# THS4302.net
KiCad netlist of a schematic drawn in Altium Designer
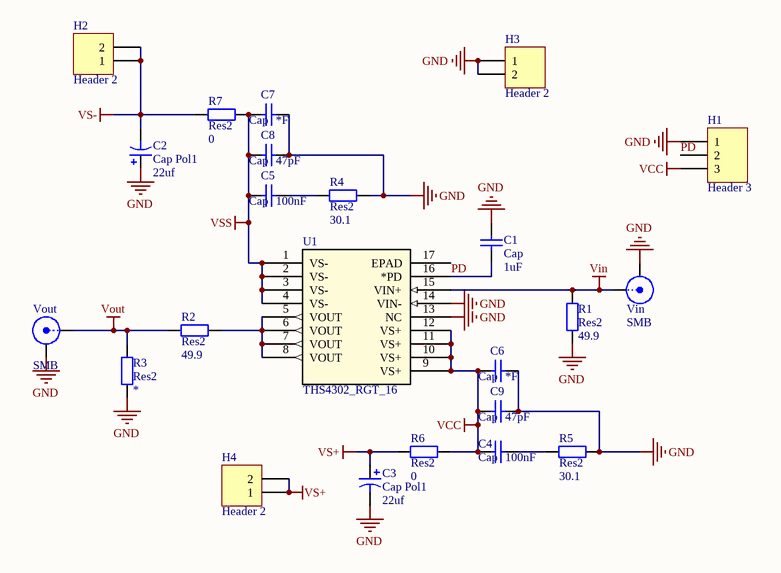
[diagram p0: THS4302.SchDoc]

(export (version "E")
  (design (tool "Eeschema 10.0.6"))
  (components
    (comp (ref "C1")
      (value "Cap")
      (footprint "0805C")
      (description "Capacitor")
      (fields (field (name "ALTIUM_VALUE") "1uF") (field (name "PUBLISHER") "Altium Limited"))
      (libsource (lib "Miscellaneous Devices") (part "Cap"))
    )
    (comp (ref "C2")
      (value "Cap Pol1")
      (footprint "CAP_SMD_3216")
      (description "Polarized Capacitor (Radial)")
      (fields (field (name "ALTIUM_VALUE") "22uf") (field (name "PUBLISHER") "Altium Limited"))
      (libsource (lib "Miscellaneous Devices") (part "Cap Pol1"))
    )
    (comp (ref "C3")
      (value "Cap Pol1")
      (footprint "CAP_SMD_3216")
      (description "Polarized Capacitor (Radial)")
      (fields (field (name "ALTIUM_VALUE") "22uf") (field (name "PUBLISHER") "Altium Limited"))
      (libsource (lib "Miscellaneous Devices") (part "Cap Pol1"))
    )
    (comp (ref "C4")
      (value "Cap")
      (footprint "0805C")
      (description "Capacitor")
      (fields (field (name "ALTIUM_VALUE") "100nF") (field (name "PUBLISHER") "Altium Limited"))
      (libsource (lib "Miscellaneous Devices") (part "Cap"))
    )
    (comp (ref "C5")
      (value "Cap")
      (footprint "0805C")
      (description "Capacitor")
      (fields (field (name "ALTIUM_VALUE") "100nF") (field (name "PUBLISHER") "Altium Limited"))
      (libsource (lib "Miscellaneous Devices") (part "Cap"))
    )
    (comp (ref "C6")
      (value "Cap")
      (footprint "CAP_SMD_3216")
      (description "Capacitor")
      (fields (field (name "ALTIUM_VALUE") "*F") (field (name "PUBLISHER") "Altium Limited"))
      (libsource (lib "Miscellaneous Devices") (part "Cap"))
    )
    (comp (ref "C7")
      (value "Cap")
      (footprint "CAP_SMD_3216")
      (description "Capacitor")
      (fields (field (name "ALTIUM_VALUE") "*F") (field (name "PUBLISHER") "Altium Limited"))
      (libsource (lib "Miscellaneous Devices") (part "Cap"))
    )
    (comp (ref "C8")
      (value "Cap")
      (footprint "0805C")
      (description "Capacitor")
      (fields (field (name "ALTIUM_VALUE") "47pF") (field (name "PUBLISHER") "Altium Limited"))
      (libsource (lib "Miscellaneous Devices") (part "Cap"))
    )
    (comp (ref "C9")
      (value "Cap")
      (footprint "0805C")
      (description "Capacitor")
      (fields (field (name "ALTIUM_VALUE") "47pF") (field (name "PUBLISHER") "Altium Limited"))
      (libsource (lib "Miscellaneous Devices") (part "Cap"))
    )
    (comp (ref "H1")
      (value "Header 3")
      (footprint "HDR1X3")
      (description "Header, 3-Pin")
      (fields (field (name "PUBLISHER") "Altium Limited"))
      (libsource (lib "Miscellaneous Connectors") (part "Header 3"))
    )
    (comp (ref "H2")
      (value "Header 2")
      (footprint "HDR1X2")
      (description "Header, 2-Pin")
      (fields (field (name "PUBLISHER") "Altium Limited"))
      (libsource (lib "Miscellaneous Connectors") (part "Header 2"))
    )
    (comp (ref "H3")
      (value "Header 2")
      (footprint "HDR1X2")
      (description "Header, 2-Pin")
      (fields (field (name "PUBLISHER") "Altium Limited"))
      (libsource (lib "") (part "Header 2_1"))
    )
    (comp (ref "H4")
      (value "Header 2")
      (footprint "HDR1X2")
      (description "Header, 2-Pin")
      (fields (field (name "PUBLISHER") "Altium Limited"))
      (libsource (lib "Miscellaneous Connectors") (part "Header 2"))
    )
    (comp (ref "R1")
      (value "Res2")
      (footprint "0805R")
      (description "Resistor")
      (fields (field (name "ALTIUM_VALUE") "49.9") (field (name "PUBLISHER") "Altium Limited"))
      (libsource (lib "") (part "Res2_1"))
    )
    (comp (ref "R2")
      (value "Res2")
      (footprint "0805R")
      (description "Resistor")
      (fields (field (name "ALTIUM_VALUE") "49.9") (field (name "PUBLISHER") "Altium Limited"))
      (libsource (lib "Miscellaneous Devices") (part "Res2"))
    )
    (comp (ref "R3")
      (value "Res2")
      (footprint "0805R")
      (description "Resistor")
      (fields (field (name "ALTIUM_VALUE") "*") (field (name "PUBLISHER") "Altium Limited"))
      (libsource (lib "") (part "Res2_2"))
    )
    (comp (ref "R4")
      (value "Res2")
      (footprint "0805R")
      (description "Resistor")
      (fields (field (name "ALTIUM_VALUE") "30.1") (field (name "PUBLISHER") "Altium Limited"))
      (libsource (lib "Miscellaneous Devices") (part "Res2"))
    )
    (comp (ref "R5")
      (value "Res2")
      (footprint "0805R")
      (description "Resistor")
      (fields (field (name "ALTIUM_VALUE") "30.1") (field (name "PUBLISHER") "Altium Limited"))
      (libsource (lib "Miscellaneous Devices") (part "Res2"))
    )
    (comp (ref "R6")
      (value "Res2")
      (footprint "0805R")
      (description "Resistor")
      (fields (field (name "ALTIUM_VALUE") "0") (field (name "PUBLISHER") "Altium Limited"))
      (libsource (lib "Miscellaneous Devices") (part "Res2"))
    )
    (comp (ref "R7")
      (value "Res2")
      (footprint "0805R")
      (description "Resistor")
      (fields (field (name "ALTIUM_VALUE") "0") (field (name "PUBLISHER") "Altium Limited"))
      (libsource (lib "Miscellaneous Devices") (part "Res2"))
    )
    (comp (ref "U1")
      (value "THS4302_RGT_16")
      (footprint "RGT16_1P45X1P45")
      (description "Imported")
      (fields
        (field (name "MANUFACTURER_PART_NUMBER") "ths4302_rgt_16")
        (field (name "GENERIC_PART_NUMBER") "THS4302")
      )
      (libsource (lib "THS4302") (part "THS4302_RGT_16"))
    )
    (comp (ref "Vin")
      (value "SMB")
      (footprint "SMB_V-RJ45")
      (description "SMB Straight Connector")
      (fields (field (name "PUBLISHER") "Altium Limited"))
      (libsource (lib "Miscellaneous Connectors") (part "SMB"))
    )
    (comp (ref "Vout")
      (value "SMB")
      (footprint "SMB_V-RJ45")
      (description "SMB Straight Connector")
      (fields (field (name "PUBLISHER") "Altium Limited"))
      (libsource (lib "Miscellaneous Connectors") (part "SMB"))
    )
  )
  (nets
    (net (code "1") (name "/PD") (class "Default")
      (node (ref "C1") (pin "1") (pinfunction "1_1") (pintype "passive"))
      (node (ref "H1") (pin "2") (pinfunction "2_2") (pintype "passive"))
      (node (ref "U1") (pin "16") (pinfunction "*PD_16") (pintype "passive"))
    )
    (net (code "2") (name "GND") (class "Default")
      (node (ref "C1") (pin "2") (pinfunction "2_2") (pintype "passive"))
      (node (ref "C2") (pin "1") (pinfunction "1_1") (pintype "passive"))
      (node (ref "C3") (pin "2") (pinfunction "2_2") (pintype "passive"))
      (node (ref "C6") (pin "2") (pinfunction "2_2") (pintype "passive"))
      (node (ref "C7") (pin "2") (pinfunction "2_2") (pintype "passive"))
      (node (ref "C8") (pin "2") (pinfunction "2_2") (pintype "passive"))
      (node (ref "C9") (pin "2") (pinfunction "2_2") (pintype "passive"))
      (node (ref "H1") (pin "1") (pinfunction "1_1") (pintype "passive"))
      (node (ref "H3") (pin "1") (pinfunction "1_1") (pintype "passive"))
      (node (ref "H3") (pin "2") (pinfunction "2_2") (pintype "passive"))
      (node (ref "R1") (pin "2") (pinfunction "2_2") (pintype "passive"))
      (node (ref "R3") (pin "1") (pinfunction "1_1") (pintype "passive"))
      (node (ref "R4") (pin "2") (pinfunction "2_2") (pintype "passive"))
      (node (ref "R5") (pin "2") (pinfunction "2_2") (pintype "passive"))
      (node (ref "U1") (pin "13") (pinfunction "NC_13") (pintype "passive"))
      (node (ref "U1") (pin "14") (pinfunction "VIN-_14") (pintype "input"))
      (node (ref "Vin") (pin "2") (pinfunction "Y_2") (pintype "passive"))
      (node (ref "Vout") (pin "2") (pinfunction "Y_2") (pintype "passive"))
    )
    (net (code "3") (name "Net-(C4-Pad2)") (class "Default")
      (node (ref "C4") (pin "2") (pinfunction "2_2") (pintype "passive"))
      (node (ref "R5") (pin "1") (pinfunction "1_1") (pintype "passive"))
    )
    (net (code "4") (name "Net-(C5-Pad2)") (class "Default")
      (node (ref "C5") (pin "2") (pinfunction "2_2") (pintype "passive"))
      (node (ref "R4") (pin "1") (pinfunction "1_1") (pintype "passive"))
    )
    (net (code "5") (name "Net-(R2-Pad2)") (class "Default")
      (node (ref "R2") (pin "2") (pinfunction "2_2") (pintype "passive"))
      (node (ref "U1") (pin "5") (pinfunction "VOUT_5") (pintype "output"))
      (node (ref "U1") (pin "6") (pinfunction "VOUT_6") (pintype "output"))
      (node (ref "U1") (pin "7") (pinfunction "VOUT_7") (pintype "output"))
      (node (ref "U1") (pin "8") (pinfunction "VOUT_8") (pintype "output"))
    )
    (net (code "6") (name "VCC") (class "Default")
      (node (ref "C4") (pin "1") (pinfunction "1_1") (pintype "passive"))
      (node (ref "C6") (pin "1") (pinfunction "1_1") (pintype "passive"))
      (node (ref "C9") (pin "1") (pinfunction "1_1") (pintype "passive"))
      (node (ref "H1") (pin "3") (pinfunction "3_3") (pintype "passive"))
      (node (ref "R6") (pin "2") (pinfunction "2_2") (pintype "passive"))
      (node (ref "U1") (pin "10") (pinfunction "VS+_10") (pintype "power_in"))
      (node (ref "U1") (pin "11") (pinfunction "VS+_11") (pintype "power_in"))
      (node (ref "U1") (pin "12") (pinfunction "VS+_12") (pintype "power_in"))
      (node (ref "U1") (pin "9") (pinfunction "VS+_9") (pintype "power_in"))
    )
    (net (code "7") (name "VS+") (class "Default")
      (node (ref "C3") (pin "1") (pinfunction "1_1") (pintype "passive"))
      (node (ref "H4") (pin "1") (pinfunction "1_1") (pintype "passive"))
      (node (ref "H4") (pin "2") (pinfunction "2_2") (pintype "passive"))
      (node (ref "R6") (pin "1") (pinfunction "1_1") (pintype "passive"))
    )
    (net (code "8") (name "VS-") (class "Default")
      (node (ref "C2") (pin "2") (pinfunction "2_2") (pintype "passive"))
      (node (ref "H2") (pin "1") (pinfunction "1_1") (pintype "passive"))
      (node (ref "H2") (pin "2") (pinfunction "2_2") (pintype "passive"))
      (node (ref "R7") (pin "1") (pinfunction "1_1") (pintype "passive"))
    )
    (net (code "9") (name "VSS") (class "Default")
      (node (ref "C5") (pin "1") (pinfunction "1_1") (pintype "passive"))
      (node (ref "C7") (pin "1") (pinfunction "1_1") (pintype "passive"))
      (node (ref "C8") (pin "1") (pinfunction "1_1") (pintype "passive"))
      (node (ref "R7") (pin "2") (pinfunction "2_2") (pintype "passive"))
      (node (ref "U1") (pin "1") (pinfunction "VS-_1") (pintype "power_in"))
      (node (ref "U1") (pin "2") (pinfunction "VS-_2") (pintype "power_in"))
      (node (ref "U1") (pin "3") (pinfunction "VS-_3") (pintype "power_in"))
      (node (ref "U1") (pin "4") (pinfunction "VS-_4") (pintype "power_in"))
    )
    (net (code "10") (name "Vin") (class "Default")
      (node (ref "R1") (pin "1") (pinfunction "1_1") (pintype "passive"))
      (node (ref "U1") (pin "15") (pinfunction "VIN+_15") (pintype "input"))
      (node (ref "Vin") (pin "1") (pinfunction "X_1") (pintype "passive"))
    )
    (net (code "11") (name "Vout") (class "Default")
      (node (ref "R2") (pin "1") (pinfunction "1_1") (pintype "passive"))
      (node (ref "R3") (pin "2") (pinfunction "2_2") (pintype "passive"))
      (node (ref "Vout") (pin "1") (pinfunction "X_1") (pintype "passive"))
    )
    (net (code "12") (name "unconnected-(U1-EPAD-Pad17)") (class "Default")
      (node (ref "U1") (pin "17") (pinfunction "EPAD_17") (pintype "passive"))
    )
  )
)
